# 24_LMS2_RX2_BB_ADC.net
KiCad netlist of a schematic drawn in Altium Designer
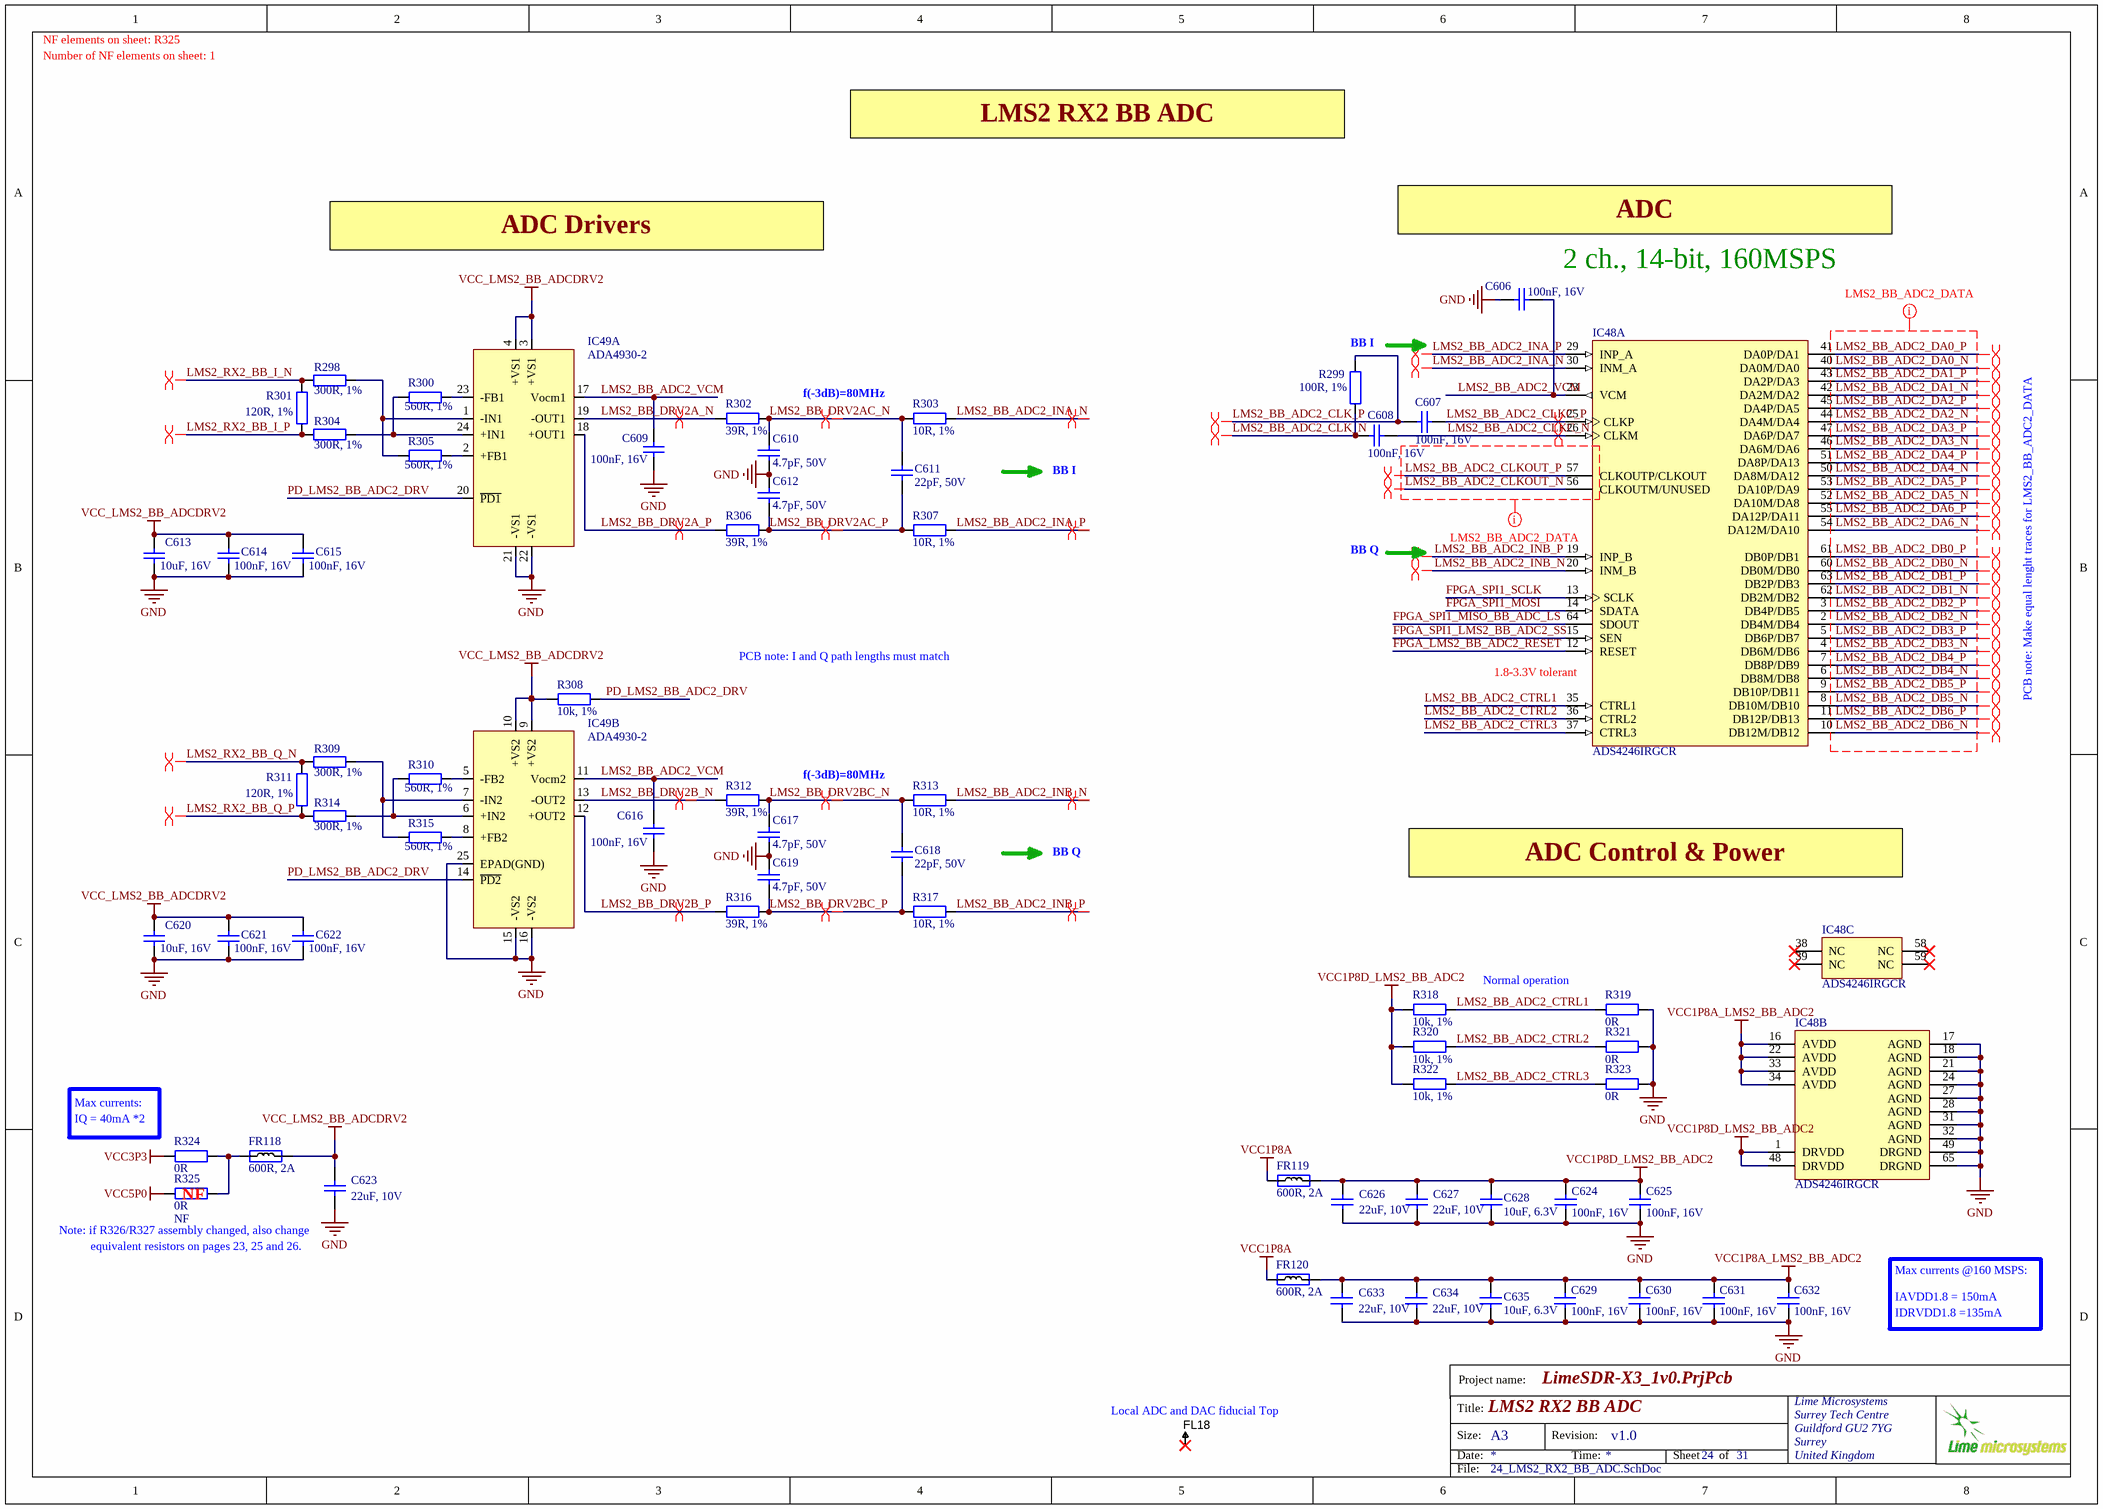
[diagram p0: 24_LMS2_RX2_BB_ADC.SchDoc]

(export (version "E")
  (design (tool "Eeschema 10.0.6"))
  (components
    (comp (ref "C606")
      (value "100nF, 16V")
      (footprint "CAP0402")
      (fields (field (name "TOLERANCE") "10 %") (field (name "MANUFACTURER") "Murata Electronics"))
      (libsource (lib "") (part "Cap_0603_5"))
    )
    (comp (ref "C607")
      (value "100nF, 16V")
      (footprint "CAP0402")
      (fields (field (name "TOLERANCE") "10 %") (field (name "MANUFACTURER") "Murata Electronics"))
      (libsource (lib "") (part "Cap_0603_5"))
    )
    (comp (ref "C608")
      (value "100nF, 16V")
      (footprint "CAP0402")
      (fields (field (name "TOLERANCE") "10 %") (field (name "MANUFACTURER") "Murata Electronics"))
      (libsource (lib "LimeFPGAboard_schLib") (part "Cap_0603"))
    )
    (comp (ref "C609")
      (value "100nF, 16V")
      (footprint "CAP0402")
      (fields (field (name "TOLERANCE") "10 %") (field (name "MANUFACTURER") "Murata Electronics"))
      (libsource (lib "LimeFPGAboard_schLib") (part "Cap_0603"))
    )
    (comp (ref "C610")
      (value "4.7pF, 50V")
      (footprint "CAP0402")
      (fields (field (name "MANUFACTURER") "MURATA"))
      (libsource (lib "LimeMicroAltiumLib_schLib") (part "Cap_0402"))
    )
    (comp (ref "C611")
      (value "22pF, 50V")
      (footprint "CAP0402")
      (fields (field (name "TOLERANCE") "±5%") (field (name "MANUFACTURER") "Yageo"))
      (libsource (lib "") (part "Cap_0402_1"))
    )
    (comp (ref "C612")
      (value "4.7pF, 50V")
      (footprint "CAP0402")
      (fields (field (name "MANUFACTURER") "MURATA"))
      (libsource (lib "LimeMicroAltiumLib_schLib") (part "Cap_0402"))
    )
    (comp (ref "C613")
      (value "10uF, 16V")
      (footprint "CAP0603")
      (fields (field (name "MANUFACTURER") "Yageo") (field (name "TOLERANCE") "±20%"))
      (libsource (lib "LimeMicroAltiumLib_schLib") (part "Cap_0603"))
    )
    (comp (ref "C614")
      (value "100nF, 16V")
      (footprint "CAP0402")
      (fields (field (name "TOLERANCE") "10 %") (field (name "MANUFACTURER") "Murata Electronics"))
      (libsource (lib "LimeFPGAboard_schLib") (part "Cap_0603"))
    )
    (comp (ref "C615")
      (value "100nF, 16V")
      (footprint "CAP0402")
      (fields (field (name "TOLERANCE") "10 %") (field (name "MANUFACTURER") "Murata Electronics"))
      (libsource (lib "LimeFPGAboard_schLib") (part "Cap_0603"))
    )
    (comp (ref "C616")
      (value "100nF, 16V")
      (footprint "CAP0402")
      (fields (field (name "TOLERANCE") "10 %") (field (name "MANUFACTURER") "Murata Electronics"))
      (libsource (lib "") (part "Cap_0603_6"))
    )
    (comp (ref "C617")
      (value "4.7pF, 50V")
      (footprint "CAP0402")
      (fields (field (name "MANUFACTURER") "MURATA"))
      (libsource (lib "LimeMicroAltiumLib_schLib") (part "Cap_0402"))
    )
    (comp (ref "C618")
      (value "22pF, 50V")
      (footprint "CAP0402")
      (fields (field (name "TOLERANCE") "±5%") (field (name "MANUFACTURER") "Yageo"))
      (libsource (lib "") (part "Cap_0402_1"))
    )
    (comp (ref "C619")
      (value "4.7pF, 50V")
      (footprint "CAP0402")
      (fields (field (name "MANUFACTURER") "MURATA"))
      (libsource (lib "LimeMicroAltiumLib_schLib") (part "Cap_0402"))
    )
    (comp (ref "C620")
      (value "10uF, 16V")
      (footprint "CAP0603")
      (fields (field (name "MANUFACTURER") "Yageo") (field (name "TOLERANCE") "±20%"))
      (libsource (lib "LimeMicroAltiumLib_schLib") (part "Cap_0603"))
    )
    (comp (ref "C621")
      (value "100nF, 16V")
      (footprint "CAP0402")
      (fields (field (name "TOLERANCE") "10 %") (field (name "MANUFACTURER") "Murata Electronics"))
      (libsource (lib "LimeFPGAboard_schLib") (part "Cap_0603"))
    )
    (comp (ref "C622")
      (value "100nF, 16V")
      (footprint "CAP0402")
      (fields (field (name "TOLERANCE") "10 %") (field (name "MANUFACTURER") "Murata Electronics"))
      (libsource (lib "LimeFPGAboard_schLib") (part "Cap_0603"))
    )
    (comp (ref "C623")
      (value "22uF, 10V")
      (footprint "CAP0603")
      (fields (field (name "TOLERANCE") "20 %") (field (name "MANUFACTURER") "TDK Corporation"))
      (libsource (lib "") (part "Cap_0603_2"))
    )
    (comp (ref "C624")
      (value "100nF, 16V")
      (footprint "CAP0402")
      (fields (field (name "TOLERANCE") "10 %") (field (name "MANUFACTURER") "Murata Electronics"))
      (libsource (lib "") (part "Cap_0603_3"))
    )
    (comp (ref "C625")
      (value "100nF, 16V")
      (footprint "CAP0402")
      (fields (field (name "TOLERANCE") "10 %") (field (name "MANUFACTURER") "Murata Electronics"))
      (libsource (lib "") (part "Cap_0603_3"))
    )
    (comp (ref "C626")
      (value "22uF, 10V")
      (footprint "CAP0603")
      (fields (field (name "TOLERANCE") "20 %") (field (name "MANUFACTURER") "TDK Corporation"))
      (libsource (lib "") (part "Cap_0603_3"))
    )
    (comp (ref "C627")
      (value "22uF, 10V")
      (footprint "CAP0603")
      (fields (field (name "TOLERANCE") "20 %") (field (name "MANUFACTURER") "TDK Corporation"))
      (libsource (lib "") (part "Cap_0603_3"))
    )
    (comp (ref "C628")
      (value "10uF, 6.3V")
      (footprint "CAP0603")
      (fields (field (name "TOLERANCE") "±20%") (field (name "MANUFACTURER") "Yageo"))
      (libsource (lib "") (part "Cap_0603_4"))
    )
    (comp (ref "C629")
      (value "100nF, 16V")
      (footprint "CAP0402")
      (fields (field (name "TOLERANCE") "10 %") (field (name "MANUFACTURER") "Murata Electronics"))
      (libsource (lib "") (part "Cap_0603_1"))
    )
    (comp (ref "C630")
      (value "100nF, 16V")
      (footprint "CAP0402")
      (fields (field (name "TOLERANCE") "10 %") (field (name "MANUFACTURER") "Murata Electronics"))
      (libsource (lib "") (part "Cap_0603_1"))
    )
    (comp (ref "C631")
      (value "100nF, 16V")
      (footprint "CAP0402")
      (fields (field (name "TOLERANCE") "10 %") (field (name "MANUFACTURER") "Murata Electronics"))
      (libsource (lib "") (part "Cap_0603_1"))
    )
    (comp (ref "C632")
      (value "100nF, 16V")
      (footprint "CAP0402")
      (fields (field (name "TOLERANCE") "10 %") (field (name "MANUFACTURER") "Murata Electronics"))
      (libsource (lib "") (part "Cap_0603_1"))
    )
    (comp (ref "C633")
      (value "22uF, 10V")
      (footprint "CAP0603")
      (fields (field (name "TOLERANCE") "20 %") (field (name "MANUFACTURER") "TDK Corporation"))
      (libsource (lib "") (part "Cap_0603_1"))
    )
    (comp (ref "C634")
      (value "22uF, 10V")
      (footprint "CAP0603")
      (fields (field (name "TOLERANCE") "20 %") (field (name "MANUFACTURER") "TDK Corporation"))
      (libsource (lib "") (part "Cap_0603_1"))
    )
    (comp (ref "C635")
      (value "10uF, 6.3V")
      (footprint "CAP0603")
      (fields (field (name "TOLERANCE") "±20%") (field (name "MANUFACTURER") "Yageo"))
      (libsource (lib "") (part "Cap_0603_7"))
    )
    (comp (ref "FL18")
      (value "Fiducial")
      (footprint "Fiducial_local")
      (libsource (lib "LimeMicroAltiumLib_schLib") (part "Fiducial"))
    )
    (comp (ref "FR118")
      (value "600R, 2A")
      (footprint "RES0805")
      (fields (field (name "MANUFACTURER") "TDK Corporation"))
      (libsource (lib "LimeMicroAltiumLib_schLib") (part "Ferrite"))
    )
    (comp (ref "FR119")
      (value "600R, 2A")
      (footprint "RES0805")
      (fields (field (name "MANUFACTURER") "TDK Corporation"))
      (libsource (lib "LimeFPGAboard_schLib") (part "Ferrite"))
    )
    (comp (ref "FR120")
      (value "600R, 2A")
      (footprint "RES0805")
      (fields (field (name "MANUFACTURER") "TDK Corporation"))
      (libsource (lib "LimeFPGAboard_schLib") (part "Ferrite"))
    )
    (comp (ref "IC48")
      (value "ADS4246IRGCR")
      (footprint "TI-RGC64-7400X7400TP_V")
      (description "14-Bit 160 MSPS Dual Low Power ADC, -40 to 85 degC, 64-pin QFN (RGC64), Green (RoHS & no Sb/Br)")
      (fields (field (name "MANUFACTURER") "Texas Instruments"))
      (libsource (lib "LimeMicroAltiumLib_schLib") (part "ADS4246IRGCR"))
    )
    (comp (ref "IC49")
      (value "ADA4930-2")
      (footprint "ADA4930-2_LFCSP-24")
      (fields (field (name "MANUFACTURER") "Analog Devices Inc."))
      (libsource (lib "") (part "ADA4930-2_1"))
    )
    (comp (ref "R298")
      (value "300R, 1%")
      (footprint "RES0402")
      (fields (field (name "TOLERANCE") "±1%") (field (name "MANUFACTURER") "Vishay Dale"))
      (libsource (lib "LimeFPGAboard_schLib") (part "Res_0402"))
    )
    (comp (ref "R299")
      (value "100R, 1%")
      (footprint "RES0402")
      (fields (field (name "TOLERANCE") "±1%") (field (name "MANUFACTURER") "Stackpole Electronics Inc."))
      (libsource (lib "LimeFPGAboard_schLib") (part "Res_0402"))
    )
    (comp (ref "R300")
      (value "560R, 1%")
      (footprint "RES0402")
      (fields (field (name "TOLERANCE") "±1%") (field (name "MANUFACTURER") "Vishay Dale"))
      (libsource (lib "LimeFPGAboard_schLib") (part "Res_0402"))
    )
    (comp (ref "R301")
      (value "120R, 1%")
      (footprint "RES0402")
      (fields (field (name "MANUFACTURER") "Yageo") (field (name "TOLERANCE") "1%"))
      (libsource (lib "") (part "Res_0402_1"))
    )
    (comp (ref "R302")
      (value "39R, 1%")
      (footprint "RES0402")
      (fields (field (name "MANUFACTURER") "Yageo") (field (name "TOLERANCE") "1%"))
      (libsource (lib "LimeMicroAltiumLib_schLib") (part "Res_0402"))
    )
    (comp (ref "R303")
      (value "10R, 1%")
      (footprint "RES0402")
      (fields (field (name "TOLERANCE") "1%"))
      (libsource (lib "LimeMicroAltiumLib_schLib") (part "Res_0402"))
    )
    (comp (ref "R304")
      (value "300R, 1%")
      (footprint "RES0402")
      (fields (field (name "TOLERANCE") "±1%") (field (name "MANUFACTURER") "Vishay Dale"))
      (libsource (lib "LimeFPGAboard_schLib") (part "Res_0402"))
    )
    (comp (ref "R305")
      (value "560R, 1%")
      (footprint "RES0402")
      (fields (field (name "TOLERANCE") "±1%") (field (name "MANUFACTURER") "Vishay Dale"))
      (libsource (lib "LimeFPGAboard_schLib") (part "Res_0402"))
    )
    (comp (ref "R306")
      (value "39R, 1%")
      (footprint "RES0402")
      (fields (field (name "MANUFACTURER") "Yageo") (field (name "TOLERANCE") "1%"))
      (libsource (lib "LimeMicroAltiumLib_schLib") (part "Res_0402"))
    )
    (comp (ref "R307")
      (value "10R, 1%")
      (footprint "RES0402")
      (fields (field (name "TOLERANCE") "1%"))
      (libsource (lib "LimeMicroAltiumLib_schLib") (part "Res_0402"))
    )
    (comp (ref "R308")
      (value "10k, 1%")
      (footprint "RES0402")
      (fields (field (name "MANUFACTURER") "Yageo") (field (name "TOLERANCE") "±1%"))
      (libsource (lib "LimeMicroAltiumLib_schLib") (part "Res_0402"))
    )
    (comp (ref "R309")
      (value "300R, 1%")
      (footprint "RES0402")
      (fields (field (name "TOLERANCE") "±1%") (field (name "MANUFACTURER") "Vishay Dale"))
      (libsource (lib "LimeFPGAboard_schLib") (part "Res_0402"))
    )
    (comp (ref "R310")
      (value "560R, 1%")
      (footprint "RES0402")
      (fields (field (name "TOLERANCE") "±1%") (field (name "MANUFACTURER") "Vishay Dale"))
      (libsource (lib "LimeFPGAboard_schLib") (part "Res_0402"))
    )
    (comp (ref "R311")
      (value "120R, 1%")
      (footprint "RES0402")
      (fields (field (name "MANUFACTURER") "Yageo") (field (name "TOLERANCE") "1%"))
      (libsource (lib "") (part "Res_0402_1"))
    )
    (comp (ref "R312")
      (value "39R, 1%")
      (footprint "RES0402")
      (fields (field (name "MANUFACTURER") "Yageo") (field (name "TOLERANCE") "1%"))
      (libsource (lib "LimeMicroAltiumLib_schLib") (part "Res_0402"))
    )
    (comp (ref "R313")
      (value "10R, 1%")
      (footprint "RES0402")
      (fields (field (name "TOLERANCE") "1%"))
      (libsource (lib "LimeMicroAltiumLib_schLib") (part "Res_0402"))
    )
    (comp (ref "R314")
      (value "300R, 1%")
      (footprint "RES0402")
      (fields (field (name "TOLERANCE") "±1%") (field (name "MANUFACTURER") "Vishay Dale"))
      (libsource (lib "LimeFPGAboard_schLib") (part "Res_0402"))
    )
    (comp (ref "R315")
      (value "560R, 1%")
      (footprint "RES0402")
      (fields (field (name "TOLERANCE") "±1%") (field (name "MANUFACTURER") "Vishay Dale"))
      (libsource (lib "LimeFPGAboard_schLib") (part "Res_0402"))
    )
    (comp (ref "R316")
      (value "39R, 1%")
      (footprint "RES0402")
      (fields (field (name "MANUFACTURER") "Yageo") (field (name "TOLERANCE") "1%"))
      (libsource (lib "LimeMicroAltiumLib_schLib") (part "Res_0402"))
    )
    (comp (ref "R317")
      (value "10R, 1%")
      (footprint "RES0402")
      (fields (field (name "TOLERANCE") "1%"))
      (libsource (lib "LimeMicroAltiumLib_schLib") (part "Res_0402"))
    )
    (comp (ref "R318")
      (value "10k, 1%")
      (footprint "RES0402")
      (fields (field (name "MANUFACTURER") "Yageo") (field (name "TOLERANCE") "±1%"))
      (libsource (lib "LimeMicroAltiumLib_schLib") (part "Res_0402"))
    )
    (comp (ref "R319")
      (value "0R")
      (footprint "RES0402")
      (fields (field (name "MANUFACTURER") "Yageo"))
      (libsource (lib "LimeFPGAboard_schLib") (part "Res_0402"))
    )
    (comp (ref "R320")
      (value "10k, 1%")
      (footprint "RES0402")
      (fields (field (name "MANUFACTURER") "Yageo") (field (name "TOLERANCE") "±1%"))
      (libsource (lib "LimeMicroAltiumLib_schLib") (part "Res_0402"))
    )
    (comp (ref "R321")
      (value "0R")
      (footprint "RES0402")
      (fields (field (name "MANUFACTURER") "Yageo"))
      (libsource (lib "LimeFPGAboard_schLib") (part "Res_0402"))
    )
    (comp (ref "R322")
      (value "10k, 1%")
      (footprint "RES0402")
      (fields (field (name "MANUFACTURER") "Yageo") (field (name "TOLERANCE") "±1%"))
      (libsource (lib "LimeMicroAltiumLib_schLib") (part "Res_0402"))
    )
    (comp (ref "R323")
      (value "0R")
      (footprint "RES0402")
      (fields (field (name "MANUFACTURER") "Yageo"))
      (libsource (lib "LimeFPGAboard_schLib") (part "Res_0402"))
    )
    (comp (ref "R324")
      (value "0R")
      (footprint "RES0402")
      (fields (field (name "MANUFACTURER") "Yageo") (field (name "TOLERANCE") "Jumper"))
      (libsource (lib "LimeMicroAltiumLib_schLib") (part "Res_0402"))
    )
    (comp (ref "R325")
      (value "0R")
      (footprint "RES0402")
      (fields
        (field (name "ASSEMBLY INFO") "NF")
        (field (name "MANUFACTURER") "Yageo")
        (field (name "TOLERANCE") "Jumper")
      )
      (libsource (lib "LimeMicroAltiumLib_schLib") (part "Res_0402"))
    )
  )
  (nets
    (net (code "1") (name "/FPGA_LMS2_BB_ADC2_RESET") (class "Default")
      (node (ref "IC48") (pin "12") (pinfunction "RESET_12") (pintype "input"))
    )
    (net (code "2") (name "/FPGA_SPI1_LMS2_BB_ADC2_SS") (class "Default")
      (node (ref "IC48") (pin "15") (pinfunction "SEN_15") (pintype "input"))
    )
    (net (code "3") (name "/FPGA_SPI1_MISO_BB_ADC_LS") (class "Default")
      (node (ref "IC48") (pin "64") (pinfunction "SDOUT_64") (pintype "tri_state"))
    )
    (net (code "4") (name "/FPGA_SPI1_MOSI") (class "Default")
      (node (ref "IC48") (pin "14") (pinfunction "SDATA_14") (pintype "input"))
    )
    (net (code "5") (name "/FPGA_SPI1_SCLK") (class "Default")
      (node (ref "IC48") (pin "13") (pinfunction "SCLK_13") (pintype "input"))
    )
    (net (code "6") (name "/LMS2_BB_ADC2_CLKC_N") (class "Default")
      (node (ref "C608") (pin "1") (pinfunction "1_1") (pintype "passive"))
      (node (ref "IC48") (pin "26") (pinfunction "CLKM_26") (pintype "input"))
    )
    (net (code "7") (name "/LMS2_BB_ADC2_CLKC_P") (class "Default")
      (node (ref "C607") (pin "1") (pinfunction "1_1") (pintype "passive"))
      (node (ref "IC48") (pin "25") (pinfunction "CLKP_25") (pintype "input"))
    )
    (net (code "8") (name "/LMS2_BB_ADC2_CLKOUT_N") (class "Default")
      (node (ref "IC48") (pin "56") (pinfunction "CLKOUTM/UNUSED_56") (pintype "tri_state"))
    )
    (net (code "9") (name "/LMS2_BB_ADC2_CLKOUT_P") (class "Default")
      (node (ref "IC48") (pin "57") (pinfunction "CLKOUTP/CLKOUT_57") (pintype "tri_state"))
    )
    (net (code "10") (name "/LMS2_BB_ADC2_CLK_N") (class "Default")
      (node (ref "C608") (pin "2") (pinfunction "2_2") (pintype "passive"))
      (node (ref "R299") (pin "1") (pinfunction "1_1") (pintype "passive"))
    )
    (net (code "11") (name "/LMS2_BB_ADC2_CLK_P") (class "Default")
      (node (ref "C607") (pin "2") (pinfunction "2_2") (pintype "passive"))
      (node (ref "R299") (pin "2") (pinfunction "2_2") (pintype "passive"))
    )
    (net (code "12") (name "/LMS2_BB_ADC2_CTRL1") (class "Default")
      (node (ref "IC48") (pin "35") (pinfunction "CTRL1_35") (pintype "input"))
      (node (ref "R318") (pin "1") (pinfunction "1_1") (pintype "passive"))
      (node (ref "R319") (pin "2") (pinfunction "2_2") (pintype "passive"))
    )
    (net (code "13") (name "/LMS2_BB_ADC2_CTRL2") (class "Default")
      (node (ref "IC48") (pin "36") (pinfunction "CTRL2_36") (pintype "input"))
      (node (ref "R320") (pin "1") (pinfunction "1_1") (pintype "passive"))
      (node (ref "R321") (pin "2") (pinfunction "2_2") (pintype "passive"))
    )
    (net (code "14") (name "/LMS2_BB_ADC2_CTRL3") (class "Default")
      (node (ref "IC48") (pin "37") (pinfunction "CTRL3_37") (pintype "input"))
      (node (ref "R322") (pin "1") (pinfunction "1_1") (pintype "passive"))
      (node (ref "R323") (pin "2") (pinfunction "2_2") (pintype "passive"))
    )
    (net (code "15") (name "/LMS2_BB_ADC2_DA0_N") (class "Default")
      (node (ref "IC48") (pin "40") (pinfunction "DA0M/DA0_40") (pintype "tri_state"))
    )
    (net (code "16") (name "/LMS2_BB_ADC2_DA0_P") (class "Default")
      (node (ref "IC48") (pin "41") (pinfunction "DA0P/DA1_41") (pintype "tri_state"))
    )
    (net (code "17") (name "/LMS2_BB_ADC2_DA1_N") (class "Default")
      (node (ref "IC48") (pin "42") (pinfunction "DA2M/DA2_42") (pintype "tri_state"))
    )
    (net (code "18") (name "/LMS2_BB_ADC2_DA1_P") (class "Default")
      (node (ref "IC48") (pin "43") (pinfunction "DA2P/DA3_43") (pintype "tri_state"))
    )
    (net (code "19") (name "/LMS2_BB_ADC2_DA2_N") (class "Default")
      (node (ref "IC48") (pin "44") (pinfunction "DA4M/DA4_44") (pintype "tri_state"))
    )
    (net (code "20") (name "/LMS2_BB_ADC2_DA2_P") (class "Default")
      (node (ref "IC48") (pin "45") (pinfunction "DA4P/DA5_45") (pintype "tri_state"))
    )
    (net (code "21") (name "/LMS2_BB_ADC2_DA3_N") (class "Default")
      (node (ref "IC48") (pin "46") (pinfunction "DA6M/DA6_46") (pintype "tri_state"))
    )
    (net (code "22") (name "/LMS2_BB_ADC2_DA3_P") (class "Default")
      (node (ref "IC48") (pin "47") (pinfunction "DA6P/DA7_47") (pintype "tri_state"))
    )
    (net (code "23") (name "/LMS2_BB_ADC2_DA4_N") (class "Default")
      (node (ref "IC48") (pin "50") (pinfunction "DA8M/DA12_50") (pintype "tri_state"))
    )
    (net (code "24") (name "/LMS2_BB_ADC2_DA4_P") (class "Default")
      (node (ref "IC48") (pin "51") (pinfunction "DA8P/DA13_51") (pintype "tri_state"))
    )
    (net (code "25") (name "/LMS2_BB_ADC2_DA5_N") (class "Default")
      (node (ref "IC48") (pin "52") (pinfunction "DA10M/DA8_52") (pintype "tri_state"))
    )
    (net (code "26") (name "/LMS2_BB_ADC2_DA5_P") (class "Default")
      (node (ref "IC48") (pin "53") (pinfunction "DA10P/DA9_53") (pintype "tri_state"))
    )
    (net (code "27") (name "/LMS2_BB_ADC2_DA6_N") (class "Default")
      (node (ref "IC48") (pin "54") (pinfunction "DA12M/DA10_54") (pintype "tri_state"))
    )
    (net (code "28") (name "/LMS2_BB_ADC2_DA6_P") (class "Default")
      (node (ref "IC48") (pin "55") (pinfunction "DA12P/DA11_55") (pintype "tri_state"))
    )
    (net (code "29") (name "/LMS2_BB_ADC2_DB0_N") (class "Default")
      (node (ref "IC48") (pin "60") (pinfunction "DB0M/DB0_60") (pintype "tri_state"))
    )
    (net (code "30") (name "/LMS2_BB_ADC2_DB0_P") (class "Default")
      (node (ref "IC48") (pin "61") (pinfunction "DB0P/DB1_61") (pintype "tri_state"))
    )
    (net (code "31") (name "/LMS2_BB_ADC2_DB1_N") (class "Default")
      (node (ref "IC48") (pin "62") (pinfunction "DB2M/DB2_62") (pintype "tri_state"))
    )
    (net (code "32") (name "/LMS2_BB_ADC2_DB1_P") (class "Default")
      (node (ref "IC48") (pin "63") (pinfunction "DB2P/DB3_63") (pintype "tri_state"))
    )
    (net (code "33") (name "/LMS2_BB_ADC2_DB2_N") (class "Default")
      (node (ref "IC48") (pin "2") (pinfunction "DB4M/DB4_2") (pintype "tri_state"))
    )
    (net (code "34") (name "/LMS2_BB_ADC2_DB2_P") (class "Default")
      (node (ref "IC48") (pin "3") (pinfunction "DB4P/DB5_3") (pintype "tri_state"))
    )
    (net (code "35") (name "/LMS2_BB_ADC2_DB3_N") (class "Default")
      (node (ref "IC48") (pin "4") (pinfunction "DB6M/DB6_4") (pintype "tri_state"))
    )
    (net (code "36") (name "/LMS2_BB_ADC2_DB3_P") (class "Default")
      (node (ref "IC48") (pin "5") (pinfunction "DB6P/DB7_5") (pintype "tri_state"))
    )
    (net (code "37") (name "/LMS2_BB_ADC2_DB4_N") (class "Default")
      (node (ref "IC48") (pin "6") (pinfunction "DB8M/DB8_6") (pintype "tri_state"))
    )
    (net (code "38") (name "/LMS2_BB_ADC2_DB4_P") (class "Default")
      (node (ref "IC48") (pin "7") (pinfunction "DB8P/DB9_7") (pintype "tri_state"))
    )
    (net (code "39") (name "/LMS2_BB_ADC2_DB5_N") (class "Default")
      (node (ref "IC48") (pin "8") (pinfunction "DB10M/DB10_8") (pintype "tri_state"))
    )
    (net (code "40") (name "/LMS2_BB_ADC2_DB5_P") (class "Default")
      (node (ref "IC48") (pin "9") (pinfunction "DB10P/DB11_9") (pintype "tri_state"))
    )
    (net (code "41") (name "/LMS2_BB_ADC2_DB6_N") (class "Default")
      (node (ref "IC48") (pin "10") (pinfunction "DB12M/DB12_10") (pintype "tri_state"))
    )
    (net (code "42") (name "/LMS2_BB_ADC2_DB6_P") (class "Default")
      (node (ref "IC48") (pin "11") (pinfunction "DB12P/DB13_11") (pintype "tri_state"))
    )
    (net (code "43") (name "/LMS2_BB_ADC2_INA_N") (class "Default")
      (node (ref "IC48") (pin "30") (pinfunction "INM_A_30") (pintype "input"))
      (node (ref "R303") (pin "1") (pinfunction "1_1") (pintype "passive"))
    )
    (net (code "44") (name "/LMS2_BB_ADC2_INA_P") (class "Default")
      (node (ref "IC48") (pin "29") (pinfunction "INP_A_29") (pintype "input"))
      (node (ref "R307") (pin "1") (pinfunction "1_1") (pintype "passive"))
    )
    (net (code "45") (name "/LMS2_BB_ADC2_INB_N") (class "Default")
      (node (ref "IC48") (pin "20") (pinfunction "INM_B_20") (pintype "input"))
      (node (ref "R313") (pin "1") (pinfunction "1_1") (pintype "passive"))
    )
    (net (code "46") (name "/LMS2_BB_ADC2_INB_P") (class "Default")
      (node (ref "IC48") (pin "19") (pinfunction "INP_B_19") (pintype "input"))
      (node (ref "R317") (pin "1") (pinfunction "1_1") (pintype "passive"))
    )
    (net (code "47") (name "/LMS2_BB_ADC2_VCM") (class "Default")
      (node (ref "C606") (pin "2") (pinfunction "2_2") (pintype "passive"))
      (node (ref "C609") (pin "1") (pinfunction "1_1") (pintype "passive"))
      (node (ref "C616") (pin "1") (pinfunction "1_1") (pintype "passive"))
      (node (ref "IC48") (pin "23") (pinfunction "VCM_23") (pintype "output"))
      (node (ref "IC49") (pin "11") (pinfunction "Vocm2_11") (pintype "input"))
      (node (ref "IC49") (pin "17") (pinfunction "Vocm1_17") (pintype "input"))
    )
    (net (code "48") (name "/LMS2_BB_DRV2AC_N") (class "Default")
      (node (ref "C610") (pin "1") (pinfunction "1_1") (pintype "passive"))
      (node (ref "C611") (pin "1") (pinfunction "1_1") (pintype "passive"))
      (node (ref "R302") (pin "1") (pinfunction "1_1") (pintype "passive"))
      (node (ref "R303") (pin "2") (pinfunction "2_2") (pintype "passive"))
    )
    (net (code "49") (name "/LMS2_BB_DRV2AC_P") (class "Default")
      (node (ref "C611") (pin "2") (pinfunction "2_2") (pintype "passive"))
      (node (ref "C612") (pin "2") (pinfunction "2_2") (pintype "passive"))
      (node (ref "R306") (pin "1") (pinfunction "1_1") (pintype "passive"))
      (node (ref "R307") (pin "2") (pinfunction "2_2") (pintype "passive"))
    )
    (net (code "50") (name "/LMS2_BB_DRV2A_N") (class "Default")
      (node (ref "IC49") (pin "19") (pinfunction "-OUT1_19") (pintype "output"))
      (node (ref "R302") (pin "2") (pinfunction "2_2") (pintype "passive"))
    )
    (net (code "51") (name "/LMS2_BB_DRV2A_P") (class "Default")
      (node (ref "IC49") (pin "18") (pinfunction "+OUT1_18") (pintype "output"))
      (node (ref "R306") (pin "2") (pinfunction "2_2") (pintype "passive"))
    )
    (net (code "52") (name "/LMS2_BB_DRV2BC_N") (class "Default")
      (node (ref "C617") (pin "1") (pinfunction "1_1") (pintype "passive"))
      (node (ref "C618") (pin "1") (pinfunction "1_1") (pintype "passive"))
      (node (ref "R312") (pin "1") (pinfunction "1_1") (pintype "passive"))
      (node (ref "R313") (pin "2") (pinfunction "2_2") (pintype "passive"))
    )
    (net (code "53") (name "/LMS2_BB_DRV2BC_P") (class "Default")
      (node (ref "C618") (pin "2") (pinfunction "2_2") (pintype "passive"))
      (node (ref "C619") (pin "2") (pinfunction "2_2") (pintype "passive"))
      (node (ref "R316") (pin "1") (pinfunction "1_1") (pintype "passive"))
      (node (ref "R317") (pin "2") (pinfunction "2_2") (pintype "passive"))
    )
    (net (code "54") (name "/LMS2_BB_DRV2B_N") (class "Default")
      (node (ref "IC49") (pin "13") (pinfunction "-OUT2_13") (pintype "output"))
      (node (ref "R312") (pin "2") (pinfunction "2_2") (pintype "passive"))
    )
    (net (code "55") (name "/LMS2_BB_DRV2B_P") (class "Default")
      (node (ref "IC49") (pin "12") (pinfunction "+OUT2_12") (pintype "output"))
      (node (ref "R316") (pin "2") (pinfunction "2_2") (pintype "passive"))
    )
    (net (code "56") (name "/LMS2_RX2_BB_I_N") (class "Default")
      (node (ref "R298") (pin "2") (pinfunction "2_2") (pintype "passive"))
      (node (ref "R301") (pin "2") (pinfunction "2_2") (pintype "passive"))
    )
    (net (code "57") (name "/LMS2_RX2_BB_I_P") (class "Default")
      (node (ref "R301") (pin "1") (pinfunction "1_1") (pintype "passive"))
      (node (ref "R304") (pin "2") (pinfunction "2_2") (pintype "passive"))
    )
    (net (code "58") (name "/LMS2_RX2_BB_Q_N") (class "Default")
      (node (ref "R309") (pin "2") (pinfunction "2_2") (pintype "passive"))
      (node (ref "R311") (pin "2") (pinfunction "2_2") (pintype "passive"))
    )
    (net (code "59") (name "/LMS2_RX2_BB_Q_P") (class "Default")
      (node (ref "R311") (pin "1") (pinfunction "1_1") (pintype "passive"))
      (node (ref "R314") (pin "2") (pinfunction "2_2") (pintype "passive"))
    )
    (net (code "60") (name "/PD_LMS2_BB_ADC2_DRV") (class "Default")
      (node (ref "IC49") (pin "14") (pinfunction "~{PD2}_14") (pintype "input"))
      (node (ref "IC49") (pin "20") (pinfunction "~{PD1}_20") (pintype "input"))
      (node (ref "R308") (pin "1") (pinfunction "1_1") (pintype "passive"))
    )
    (net (code "61") (name "GND") (class "Default")
      (node (ref "C606") (pin "1") (pinfunction "1_1") (pintype "passive"))
      (node (ref "C609") (pin "2") (pinfunction "2_2") (pintype "passive"))
      (node (ref "C610") (pin "2") (pinfunction "2_2") (pintype "passive"))
      (node (ref "C612") (pin "1") (pinfunction "1_1") (pintype "passive"))
      (node (ref "C613") (pin "1") (pinfunction "1_1") (pintype "passive"))
      (node (ref "C614") (pin "2") (pinfunction "2_2") (pintype "passive"))
      (node (ref "C615") (pin "2") (pinfunction "2_2") (pintype "passive"))
      (node (ref "C616") (pin "2") (pinfunction "2_2") (pintype "passive"))
      (node (ref "C617") (pin "2") (pinfunction "2_2") (pintype "passive"))
      (node (ref "C619") (pin "1") (pinfunction "1_1") (pintype "passive"))
      (node (ref "C620") (pin "1") (pinfunction "1_1") (pintype "passive"))
      (node (ref "C621") (pin "2") (pinfunction "2_2") (pintype "passive"))
      (node (ref "C622") (pin "2") (pinfunction "2_2") (pintype "passive"))
      (node (ref "C623") (pin "1") (pinfunction "1_1") (pintype "passive"))
      (node (ref "C624") (pin "1") (pinfunction "1_1") (pintype "passive"))
      (node (ref "C625") (pin "1") (pinfunction "1_1") (pintype "passive"))
      (node (ref "C626") (pin "1") (pinfunction "1_1") (pintype "passive"))
      (node (ref "C627") (pin "1") (pinfunction "1_1") (pintype "passive"))
      (node (ref "C628") (pin "2") (pinfunction "2_2") (pintype "passive"))
      (node (ref "C629") (pin "1") (pinfunction "1_1") (pintype "passive"))
      (node (ref "C630") (pin "1") (pinfunction "1_1") (pintype "passive"))
      (node (ref "C631") (pin "1") (pinfunction "1_1") (pintype "passive"))
      (node (ref "C632") (pin "1") (pinfunction "1_1") (pintype "passive"))
      (node (ref "C633") (pin "1") (pinfunction "1_1") (pintype "passive"))
      (node (ref "C634") (pin "1") (pinfunction "1_1") (pintype "passive"))
      (node (ref "C635") (pin "2") (pinfunction "2_2") (pintype "passive"))
      (node (ref "IC48") (pin "17") (pinfunction "AGND_17") (pintype "power_in"))
      (node (ref "IC48") (pin "18") (pinfunction "AGND_18") (pintype "power_in"))
      (node (ref "IC48") (pin "21") (pinfunction "AGND_21") (pintype "power_in"))
      (node (ref "IC48") (pin "24") (pinfunction "AGND_24") (pintype "power_in"))
      (node (ref "IC48") (pin "27") (pinfunction "AGND_27") (pintype "power_in"))
      (node (ref "IC48") (pin "28") (pinfunction "AGND_28") (pintype "power_in"))
      (node (ref "IC48") (pin "31") (pinfunction "AGND_31") (pintype "power_in"))
      (node (ref "IC48") (pin "32") (pinfunction "AGND_32") (pintype "power_in"))
      (node (ref "IC48") (pin "49") (pinfunction "DRGND_49") (pintype "power_in"))
      (node (ref "IC48") (pin "65") (pinfunction "DRGND_65") (pintype "power_in"))
      (node (ref "IC49") (pin "15") (pinfunction "-VS2_15") (pintype "power_in"))
      (node (ref "IC49") (pin "16") (pinfunction "-VS2_16") (pintype "power_in"))
      (node (ref "IC49") (pin "21") (pinfunction "-VS1_21") (pintype "power_in"))
      (node (ref "IC49") (pin "22") (pinfunction "-VS1_22") (pintype "power_in"))
      (node (ref "IC49") (pin "25") (pinfunction "EPAD(GND)_25") (pintype "passive"))
      (node (ref "R319") (pin "1") (pinfunction "1_1") (pintype "passive"))
      (node (ref "R321") (pin "1") (pinfunction "1_1") (pintype "passive"))
      (node (ref "R323") (pin "1") (pinfunction "1_1") (pintype "passive"))
    )
    (net (code "62") (name "Net-(FR118-Pad1)") (class "Default")
      (node (ref "FR118") (pin "1") (pinfunction "1_1") (pintype "passive"))
      (node (ref "R324") (pin "1") (pinfunction "1_1") (pintype "passive"))
      (node (ref "R325") (pin "1") (pinfunction "1_1") (pintype "passive"))
    )
    (net (code "63") (name "Net-(IC49A-+FB1)") (class "Default")
      (node (ref "IC49") (pin "2") (pinfunction "+FB1_2") (pintype "output"))
      (node (ref "R305") (pin "1") (pinfunction "1_1") (pintype "passive"))
    )
    (net (code "64") (name "Net-(IC49A-+IN1)") (class "Default")
      (node (ref "IC49") (pin "24") (pinfunction "+IN1_24") (pintype "input"))
      (node (ref "R300") (pin "2") (pinfunction "2_2") (pintype "passive"))
      (node (ref "R304") (pin "1") (pinfunction "1_1") (pintype "passive"))
    )
    (net (code "65") (name "Net-(IC49A--FB1)") (class "Default")
      (node (ref "IC49") (pin "23") (pinfunction "-FB1_23") (pintype "output"))
      (node (ref "R300") (pin "1") (pinfunction "1_1") (pintype "passive"))
    )
    (net (code "66") (name "Net-(IC49A--IN1)") (class "Default")
      (node (ref "IC49") (pin "1") (pinfunction "-IN1_1") (pintype "input"))
      (node (ref "R298") (pin "1") (pinfunction "1_1") (pintype "passive"))
      (node (ref "R305") (pin "2") (pinfunction "2_2") (pintype "passive"))
    )
    (net (code "67") (name "Net-(IC49B-+FB2)") (class "Default")
      (node (ref "IC49") (pin "8") (pinfunction "+FB2_8") (pintype "output"))
      (node (ref "R315") (pin "1") (pinfunction "1_1") (pintype "passive"))
    )
    (net (code "68") (name "Net-(IC49B-+IN2)") (class "Default")
      (node (ref "IC49") (pin "6") (pinfunction "+IN2_6") (pintype "input"))
      (node (ref "R310") (pin "2") (pinfunction "2_2") (pintype "passive"))
      (node (ref "R314") (pin "1") (pinfunction "1_1") (pintype "passive"))
    )
    (net (code "69") (name "Net-(IC49B--FB2)") (class "Default")
      (node (ref "IC49") (pin "5") (pinfunction "-FB2_5") (pintype "output"))
      (node (ref "R310") (pin "1") (pinfunction "1_1") (pintype "passive"))
    )
    (net (code "70") (name "Net-(IC49B--IN2)") (class "Default")
      (node (ref "IC49") (pin "7") (pinfunction "-IN2_7") (pintype "input"))
      (node (ref "R309") (pin "1") (pinfunction "1_1") (pintype "passive"))
      (node (ref "R315") (pin "2") (pinfunction "2_2") (pintype "passive"))
    )
    (net (code "71") (name "VCC1P8A") (class "Default")
      (node (ref "FR119") (pin "1") (pinfunction "1_1") (pintype "passive"))
      (node (ref "FR120") (pin "1") (pinfunction "1_1") (pintype "passive"))
    )
    (net (code "72") (name "VCC1P8A_LMS2_BB_ADC2") (class "Default")
      (node (ref "C629") (pin "2") (pinfunction "2_2") (pintype "passive"))
      (node (ref "C630") (pin "2") (pinfunction "2_2") (pintype "passive"))
      (node (ref "C631") (pin "2") (pinfunction "2_2") (pintype "passive"))
      (node (ref "C632") (pin "2") (pinfunction "2_2") (pintype "passive"))
      (node (ref "C633") (pin "2") (pinfunction "2_2") (pintype "passive"))
      (node (ref "C634") (pin "2") (pinfunction "2_2") (pintype "passive"))
      (node (ref "C635") (pin "1") (pinfunction "1_1") (pintype "passive"))
      (node (ref "FR120") (pin "2") (pinfunction "2_2") (pintype "passive"))
      (node (ref "IC48") (pin "16") (pinfunction "AVDD_16") (pintype "power_in"))
      (node (ref "IC48") (pin "22") (pinfunction "AVDD_22") (pintype "power_in"))
      (node (ref "IC48") (pin "33") (pinfunction "AVDD_33") (pintype "power_in"))
      (node (ref "IC48") (pin "34") (pinfunction "AVDD_34") (pintype "power_in"))
    )
    (net (code "73") (name "VCC1P8D_LMS2_BB_ADC2") (class "Default")
      (node (ref "C624") (pin "2") (pinfunction "2_2") (pintype "passive"))
      (node (ref "C625") (pin "2") (pinfunction "2_2") (pintype "passive"))
      (node (ref "C626") (pin "2") (pinfunction "2_2") (pintype "passive"))
      (node (ref "C627") (pin "2") (pinfunction "2_2") (pintype "passive"))
      (node (ref "C628") (pin "1") (pinfunction "1_1") (pintype "passive"))
      (node (ref "FR119") (pin "2") (pinfunction "2_2") (pintype "passive"))
      (node (ref "IC48") (pin "1") (pinfunction "DRVDD_1") (pintype "power_in"))
      (node (ref "IC48") (pin "48") (pinfunction "DRVDD_48") (pintype "power_in"))
      (node (ref "R318") (pin "2") (pinfunction "2_2") (pintype "passive"))
      (node (ref "R320") (pin "2") (pinfunction "2_2") (pintype "passive"))
      (node (ref "R322") (pin "2") (pinfunction "2_2") (pintype "passive"))
    )
    (net (code "74") (name "VCC3P3") (class "Default")
      (node (ref "R324") (pin "2") (pinfunction "2_2") (pintype "passive"))
    )
    (net (code "75") (name "VCC5P0") (class "Default")
      (node (ref "R325") (pin "2") (pinfunction "2_2") (pintype "passive"))
    )
    (net (code "76") (name "VCC_LMS2_BB_ADCDRV2") (class "Default")
      (node (ref "C613") (pin "2") (pinfunction "2_2") (pintype "passive"))
      (node (ref "C614") (pin "1") (pinfunction "1_1") (pintype "passive"))
      (node (ref "C615") (pin "1") (pinfunction "1_1") (pintype "passive"))
      (node (ref "C620") (pin "2") (pinfunction "2_2") (pintype "passive"))
      (node (ref "C621") (pin "1") (pinfunction "1_1") (pintype "passive"))
      (node (ref "C622") (pin "1") (pinfunction "1_1") (pintype "passive"))
      (node (ref "C623") (pin "2") (pinfunction "2_2") (pintype "passive"))
      (node (ref "FR118") (pin "2") (pinfunction "2_2") (pintype "passive"))
      (node (ref "IC49") (pin "10") (pinfunction "+VS2_10") (pintype "power_in"))
      (node (ref "IC49") (pin "3") (pinfunction "+VS1_3") (pintype "power_in"))
      (node (ref "IC49") (pin "4") (pinfunction "+VS1_4") (pintype "power_in"))
      (node (ref "IC49") (pin "9") (pinfunction "+VS2_9") (pintype "power_in"))
      (node (ref "R308") (pin "2") (pinfunction "2_2") (pintype "passive"))
    )
    (net (code "77") (name "unconnected-(FL18-Pad1)") (class "Default")
      (node (ref "FL18") (pin "1") (pintype "passive+no_connect"))
    )
    (net (code "78") (name "unconnected-(IC48C-NC-Pad38)") (class "Default")
      (node (ref "IC48") (pin "38") (pinfunction "NC_38") (pintype "passive+no_connect"))
    )
    (net (code "79") (name "unconnected-(IC48C-NC-Pad39)") (class "Default")
      (node (ref "IC48") (pin "39") (pinfunction "NC_39") (pintype "passive+no_connect"))
    )
    (net (code "80") (name "unconnected-(IC48C-NC-Pad58)") (class "Default")
      (node (ref "IC48") (pin "58") (pinfunction "NC_58") (pintype "passive+no_connect"))
    )
    (net (code "81") (name "unconnected-(IC48C-NC-Pad59)") (class "Default")
      (node (ref "IC48") (pin "59") (pinfunction "NC_59") (pintype "passive+no_connect"))
    )
  )
)
